# TDA2030.net
KiCad netlist of a schematic drawn in Altium Designer
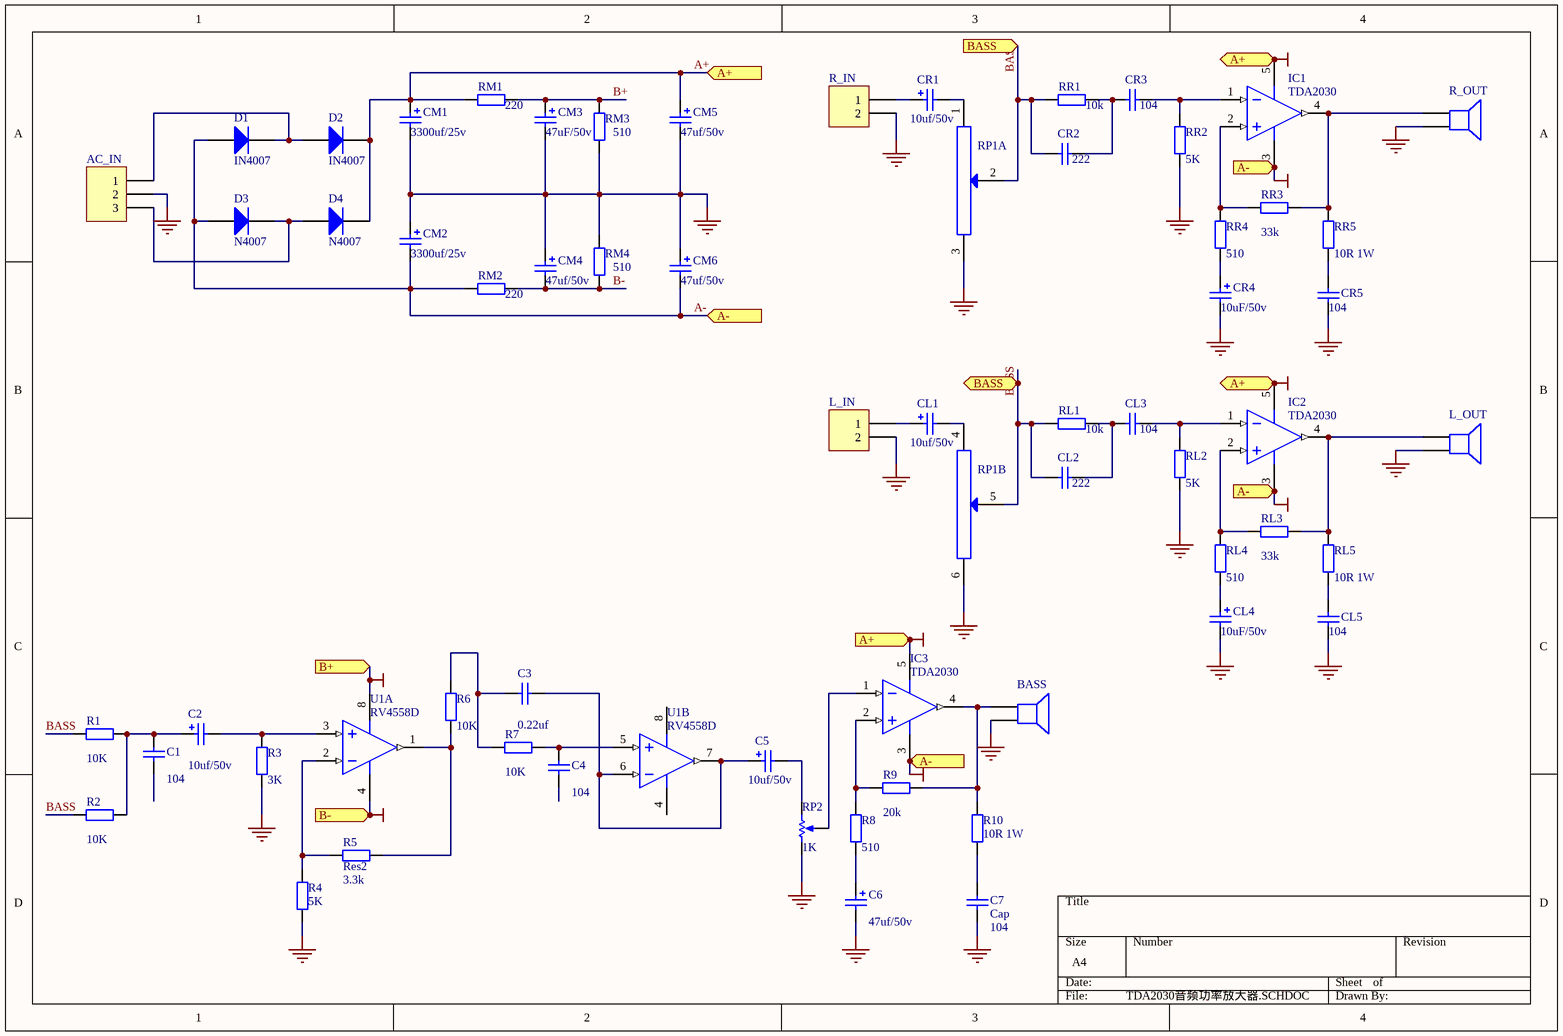
[diagram p0: TDA2030音频功率放大器.SCHDOC]

(export (version "E")
  (design (tool "Eeschema 10.0.6"))
  (components
    (comp (ref "AC_IN")
      (value "Header 3")
      (footprint "HDR1X3")
      (description "Header, 3-Pin")
      (fields (field (name "PUBLISHER") "Altium Limited"))
      (libsource (lib "Miscellaneous Connectors") (part "Header 3"))
    )
    (comp (ref "BASS")
      (value "Speaker")
      (footprint "PIN2")
      (description "Loudspeaker")
      (fields (field (name "PUBLISHER") "Altium Limited"))
      (libsource (lib "Miscellaneous Devices") (part "Speaker"))
    )
    (comp (ref "C1")
      (value "104")
      (footprint "RAD-0.3")
      (description "Capacitor")
      (fields (field (name "Comment") "Cap") (field (name "PUBLISHER") "Altium Limited"))
      (libsource (lib "Miscellaneous Devices") (part "Cap"))
    )
    (comp (ref "C2")
      (value "10uf/50v")
      (footprint "POLAR0.8")
      (description "Polarized Capacitor (Axial)")
      (fields (field (name "Comment") "Cap Pol2") (field (name "PUBLISHER") "Altium Limited"))
      (libsource (lib "Miscellaneous Devices") (part "Cap Pol2"))
    )
    (comp (ref "C3")
      (value "0.22uf")
      (footprint "RAD-0.3")
      (description "Capacitor")
      (fields (field (name "Comment") "Cap") (field (name "PUBLISHER") "Altium Limited"))
      (libsource (lib "Miscellaneous Devices") (part "Cap"))
    )
    (comp (ref "C4")
      (value "104")
      (footprint "RAD-0.3")
      (description "Capacitor")
      (fields (field (name "Comment") "Cap") (field (name "PUBLISHER") "Altium Limited"))
      (libsource (lib "Miscellaneous Devices") (part "Cap"))
    )
    (comp (ref "C5")
      (value "10uf/50v")
      (footprint "POLAR0.8")
      (description "Polarized Capacitor (Axial)")
      (fields (field (name "Comment") "Cap Pol2") (field (name "PUBLISHER") "Altium Limited"))
      (libsource (lib "Miscellaneous Devices") (part "Cap Pol2"))
    )
    (comp (ref "C6")
      (value "47uf/50v")
      (footprint "POLAR0.8")
      (description "Polarized Capacitor (Axial)")
      (fields (field (name "Comment") "Cap Pol2") (field (name "PUBLISHER") "Altium Limited"))
      (libsource (lib "Miscellaneous Devices") (part "Cap Pol2"))
    )
    (comp (ref "C7")
      (value "Cap")
      (footprint "RAD-0.3")
      (description "Capacitor")
      (fields (field (name "ALTIUM_VALUE") "104") (field (name "PUBLISHER") "Altium Limited"))
      (libsource (lib "Miscellaneous Devices") (part "Cap"))
    )
    (comp (ref "CL1")
      (value "10uf/50v")
      (footprint "POLAR0.8")
      (description "Polarized Capacitor (Axial)")
      (fields (field (name "Comment") "Cap Pol2") (field (name "PUBLISHER") "Altium Limited"))
      (libsource (lib "Miscellaneous Devices") (part "Cap Pol2"))
    )
    (comp (ref "CL2")
      (value "222")
      (footprint "RAD-0.3")
      (description "Capacitor")
      (fields (field (name "Comment") "Cap") (field (name "PUBLISHER") "Altium Limited"))
      (libsource (lib "Miscellaneous Devices") (part "Cap"))
    )
    (comp (ref "CL3")
      (value "104")
      (footprint "RAD-0.3")
      (description "Capacitor")
      (fields (field (name "Comment") "Cap") (field (name "PUBLISHER") "Altium Limited"))
      (libsource (lib "Miscellaneous Devices") (part "Cap"))
    )
    (comp (ref "CL4")
      (value "10uF/50v")
      (footprint "POLAR0.8")
      (description "Polarized Capacitor (Axial)")
      (fields (field (name "Comment") "Cap Pol2") (field (name "PUBLISHER") "Altium Limited"))
      (libsource (lib "Miscellaneous Devices") (part "Cap Pol2"))
    )
    (comp (ref "CL5")
      (value "104")
      (footprint "RAD-0.3")
      (description "Capacitor")
      (fields (field (name "Comment") "Cap") (field (name "PUBLISHER") "Altium Limited"))
      (libsource (lib "Miscellaneous Devices") (part "Cap"))
    )
    (comp (ref "CM1")
      (value "3300uf/25v")
      (footprint "POLAR0.8")
      (description "Polarized Capacitor (Axial)")
      (fields (field (name "Comment") "Cap Pol2") (field (name "PUBLISHER") "Altium Limited"))
      (libsource (lib "Miscellaneous Devices") (part "Cap Pol2"))
    )
    (comp (ref "CM2")
      (value "3300uf/25v")
      (footprint "POLAR0.8")
      (description "Polarized Capacitor (Axial)")
      (fields (field (name "Comment") "Cap Pol2") (field (name "PUBLISHER") "Altium Limited"))
      (libsource (lib "Miscellaneous Devices") (part "Cap Pol2"))
    )
    (comp (ref "CM3")
      (value "47uF/50v")
      (footprint "POLAR0.8")
      (description "Polarized Capacitor (Axial)")
      (fields (field (name "Comment") "Cap Pol2") (field (name "PUBLISHER") "Altium Limited"))
      (libsource (lib "Miscellaneous Devices") (part "Cap Pol2"))
    )
    (comp (ref "CM4")
      (value "47uf/50v")
      (footprint "POLAR0.8")
      (description "Polarized Capacitor (Axial)")
      (fields (field (name "Comment") "Cap Pol2") (field (name "PUBLISHER") "Altium Limited"))
      (libsource (lib "Miscellaneous Devices") (part "Cap Pol2"))
    )
    (comp (ref "CM5")
      (value "47uf/50v")
      (footprint "POLAR0.8")
      (description "Polarized Capacitor (Axial)")
      (fields (field (name "Comment") "Cap Pol2") (field (name "PUBLISHER") "Altium Limited"))
      (libsource (lib "Miscellaneous Devices") (part "Cap Pol2"))
    )
    (comp (ref "CM6")
      (value "47uf/50v")
      (footprint "POLAR0.8")
      (description "Polarized Capacitor (Axial)")
      (fields (field (name "Comment") "Cap Pol2") (field (name "PUBLISHER") "Altium Limited"))
      (libsource (lib "Miscellaneous Devices") (part "Cap Pol2"))
    )
    (comp (ref "CR1")
      (value "10uf/50v")
      (footprint "POLAR0.8")
      (description "Polarized Capacitor (Axial)")
      (fields (field (name "Comment") "Cap Pol2") (field (name "PUBLISHER") "Altium Limited"))
      (libsource (lib "Miscellaneous Devices") (part "Cap Pol2"))
    )
    (comp (ref "CR2")
      (value "222")
      (footprint "RAD-0.3")
      (description "Capacitor")
      (fields (field (name "Comment") "Cap") (field (name "PUBLISHER") "Altium Limited"))
      (libsource (lib "Miscellaneous Devices") (part "Cap"))
    )
    (comp (ref "CR3")
      (value "104")
      (footprint "RAD-0.3")
      (description "Capacitor")
      (fields (field (name "Comment") "Cap") (field (name "PUBLISHER") "Altium Limited"))
      (libsource (lib "Miscellaneous Devices") (part "Cap"))
    )
    (comp (ref "CR4")
      (value "10uF/50v")
      (footprint "POLAR0.8")
      (description "Polarized Capacitor (Axial)")
      (fields (field (name "Comment") "Cap Pol2") (field (name "PUBLISHER") "Altium Limited"))
      (libsource (lib "Miscellaneous Devices") (part "Cap Pol2"))
    )
    (comp (ref "CR5")
      (value "104")
      (footprint "RAD-0.3")
      (description "Capacitor")
      (fields (field (name "Comment") "Cap") (field (name "PUBLISHER") "Altium Limited"))
      (libsource (lib "Miscellaneous Devices") (part "Cap"))
    )
    (comp (ref "D1")
      (value "IN4007")
      (footprint "DIO10.46-5.3x2.8")
      (description "1 Amp General Purpose Rectifier")
      (fields (field (name "PUBLISHER") "Altium Limited"))
      (libsource (lib "Miscellaneous Devices") (part "Diode 1N4007"))
    )
    (comp (ref "D2")
      (value "IN4007")
      (footprint "DIO10.46-5.3x2.8")
      (description "1 Amp General Purpose Rectifier")
      (fields (field (name "PUBLISHER") "Altium Limited"))
      (libsource (lib "Miscellaneous Devices") (part "Diode 1N4007"))
    )
    (comp (ref "D3")
      (value "N4007")
      (footprint "DIO10.46-5.3x2.8")
      (description "1 Amp General Purpose Rectifier")
      (fields (field (name "PUBLISHER") "Altium Limited"))
      (libsource (lib "Miscellaneous Devices") (part "Diode 1N4007"))
    )
    (comp (ref "D4")
      (value "N4007")
      (footprint "DIO10.46-5.3x2.8")
      (description "1 Amp General Purpose Rectifier")
      (fields (field (name "PUBLISHER") "Altium Limited"))
      (libsource (lib "Miscellaneous Devices") (part "Diode 1N4007"))
    )
    (comp (ref "IC1") (value "TDA2030") (libsource (lib "TDA2030音频功率放大器") (part "TDA2030")))
    (comp (ref "IC2") (value "TDA2030") (libsource (lib "TDA2030音频功率放大器") (part "TDA2030")))
    (comp (ref "IC3") (value "TDA2030") (libsource (lib "TDA2030音频功率放大器") (part "TDA2030")))
    (comp (ref "L_IN")
      (value "Header 2")
      (footprint "HDR1X2")
      (description "Header, 2-Pin")
      (fields (field (name "PUBLISHER") "Altium Limited"))
      (libsource (lib "Miscellaneous Connectors") (part "Header 2"))
    )
    (comp (ref "L_OUT")
      (value "Speaker")
      (footprint "PIN2")
      (description "Loudspeaker")
      (fields (field (name "PUBLISHER") "Altium Limited"))
      (libsource (lib "Miscellaneous Devices") (part "Speaker"))
    )
    (comp (ref "R1")
      (value "10K")
      (footprint "AXIAL-0.4")
      (description "Resistor")
      (fields (field (name "Comment") "Res2") (field (name "PUBLISHER") "Altium Limited"))
      (libsource (lib "Miscellaneous Devices") (part "Res2"))
    )
    (comp (ref "R2")
      (value "10K")
      (footprint "AXIAL-0.4")
      (description "Resistor")
      (fields (field (name "Comment") "Res2") (field (name "PUBLISHER") "Altium Limited"))
      (libsource (lib "Miscellaneous Devices") (part "Res2"))
    )
    (comp (ref "R3")
      (value "3K")
      (footprint "AXIAL-0.4")
      (description "Resistor")
      (fields (field (name "Comment") "Res2") (field (name "PUBLISHER") "Altium Limited"))
      (libsource (lib "") (part "Res2_1"))
    )
    (comp (ref "R4")
      (value "5K")
      (footprint "AXIAL-0.4")
      (description "Resistor")
      (fields (field (name "Comment") "Res2") (field (name "PUBLISHER") "Altium Limited"))
      (libsource (lib "") (part "Res2_1"))
    )
    (comp (ref "R5")
      (value "Res2")
      (footprint "AXIAL-0.4")
      (description "Resistor")
      (fields (field (name "ALTIUM_VALUE") "3.3k") (field (name "PUBLISHER") "Altium Limited"))
      (libsource (lib "") (part "Res2_3"))
    )
    (comp (ref "R6")
      (value "10K")
      (footprint "AXIAL-0.4")
      (description "Resistor")
      (fields (field (name "Comment") "Res2") (field (name "PUBLISHER") "Altium Limited"))
      (libsource (lib "") (part "Res2_2"))
    )
    (comp (ref "R7")
      (value "10K")
      (footprint "AXIAL-0.4")
      (description "Resistor")
      (fields (field (name "Comment") "Res2") (field (name "PUBLISHER") "Altium Limited"))
      (libsource (lib "Miscellaneous Devices") (part "Res2"))
    )
    (comp (ref "R8")
      (value "510")
      (footprint "AXIAL-0.4")
      (description "Resistor")
      (fields (field (name "Comment") "Res2") (field (name "PUBLISHER") "Altium Limited"))
      (libsource (lib "") (part "Res2_1"))
    )
    (comp (ref "R9")
      (value "20k")
      (footprint "AXIAL-0.4")
      (description "Resistor")
      (fields (field (name "Comment") "Res2") (field (name "PUBLISHER") "Altium Limited"))
      (libsource (lib "Miscellaneous Devices") (part "Res2"))
    )
    (comp (ref "R10")
      (value "10R 1W")
      (footprint "AXIAL-0.4")
      (description "Resistor")
      (fields (field (name "Comment") "Res2") (field (name "PUBLISHER") "Altium Limited"))
      (libsource (lib "") (part "Res2_1"))
    )
    (comp (ref "RL1")
      (value "10k")
      (footprint "AXIAL-0.4")
      (description "Resistor")
      (fields (field (name "Comment") "Res2") (field (name "PUBLISHER") "Altium Limited"))
      (libsource (lib "Miscellaneous Devices") (part "Res2"))
    )
    (comp (ref "RL2")
      (value "5K")
      (footprint "AXIAL-0.4")
      (description "Resistor")
      (fields (field (name "Comment") "Res2") (field (name "PUBLISHER") "Altium Limited"))
      (libsource (lib "") (part "Res2_1"))
    )
    (comp (ref "RL3")
      (value "33k")
      (footprint "AXIAL-0.4")
      (description "Resistor")
      (fields (field (name "Comment") "Res2") (field (name "PUBLISHER") "Altium Limited"))
      (libsource (lib "") (part "Res2_3"))
    )
    (comp (ref "RL4")
      (value "510")
      (footprint "AXIAL-0.4")
      (description "Resistor")
      (fields (field (name "Comment") "Res2") (field (name "PUBLISHER") "Altium Limited"))
      (libsource (lib "") (part "Res2_1"))
    )
    (comp (ref "RL5")
      (value "10R 1W")
      (footprint "AXIAL-0.4")
      (description "Resistor")
      (fields (field (name "Comment") "Res2") (field (name "PUBLISHER") "Altium Limited"))
      (libsource (lib "") (part "Res2_2"))
    )
    (comp (ref "RM1")
      (value "220")
      (footprint "AXIAL-0.4")
      (description "Resistor")
      (fields (field (name "Comment") "Res2") (field (name "PUBLISHER") "Altium Limited"))
      (libsource (lib "Miscellaneous Devices") (part "Res2"))
    )
    (comp (ref "RM2")
      (value "220")
      (footprint "AXIAL-0.4")
      (description "Resistor")
      (fields (field (name "Comment") "Res2") (field (name "PUBLISHER") "Altium Limited"))
      (libsource (lib "Miscellaneous Devices") (part "Res2"))
    )
    (comp (ref "RM3")
      (value "510")
      (footprint "AXIAL-0.4")
      (description "Resistor")
      (fields (field (name "Comment") "Res2") (field (name "PUBLISHER") "Altium Limited"))
      (libsource (lib "") (part "Res2_1"))
    )
    (comp (ref "RM4")
      (value "510")
      (footprint "AXIAL-0.4")
      (description "Resistor")
      (fields (field (name "Comment") "Res2") (field (name "PUBLISHER") "Altium Limited"))
      (libsource (lib "") (part "Res2_1"))
    )
    (comp (ref "RP1") (value "POT3") (footprint "BK09") (libsource (lib "47耳放设计") (part "POT3")))
    (comp (ref "RP2")
      (value "1K")
      (footprint "VR5")
      (description "Potentiometer")
      (fields (field (name "Comment") "POT2") (field (name "PUBLISHER") "Altium Limited"))
      (libsource (lib "Miscellaneous Devices") (part "RPot"))
    )
    (comp (ref "RR1")
      (value "10k")
      (footprint "AXIAL-0.4")
      (description "Resistor")
      (fields (field (name "Comment") "Res2") (field (name "PUBLISHER") "Altium Limited"))
      (libsource (lib "Miscellaneous Devices") (part "Res2"))
    )
    (comp (ref "RR2")
      (value "5K")
      (footprint "AXIAL-0.4")
      (description "Resistor")
      (fields (field (name "Comment") "Res2") (field (name "PUBLISHER") "Altium Limited"))
      (libsource (lib "") (part "Res2_1"))
    )
    (comp (ref "RR3")
      (value "33k")
      (footprint "AXIAL-0.4")
      (description "Resistor")
      (fields (field (name "Comment") "Res2") (field (name "PUBLISHER") "Altium Limited"))
      (libsource (lib "") (part "Res2_3"))
    )
    (comp (ref "RR4")
      (value "510")
      (footprint "AXIAL-0.4")
      (description "Resistor")
      (fields (field (name "Comment") "Res2") (field (name "PUBLISHER") "Altium Limited"))
      (libsource (lib "") (part "Res2_1"))
    )
    (comp (ref "RR5")
      (value "10R 1W")
      (footprint "AXIAL-0.4")
      (description "Resistor")
      (fields (field (name "Comment") "Res2") (field (name "PUBLISHER") "Altium Limited"))
      (libsource (lib "") (part "Res2_2"))
    )
    (comp (ref "R_IN")
      (value "Header 2")
      (footprint "HDR1X2")
      (description "Header, 2-Pin")
      (fields (field (name "PUBLISHER") "Altium Limited"))
      (libsource (lib "Miscellaneous Connectors") (part "Header 2"))
    )
    (comp (ref "R_OUT")
      (value "Speaker")
      (footprint "PIN2")
      (description "Loudspeaker")
      (fields (field (name "PUBLISHER") "Altium Limited"))
      (libsource (lib "Miscellaneous Devices") (part "Speaker"))
    )
    (comp (ref "U1")
      (value "RV4558D")
      (footprint "D008")
      (description "Dual High-Performance Operational Amplifier")
      (fields (field (name "PUBLISHER") "Altium Limited"))
      (libsource (lib "TDA2030音频功率放大器") (part "RV4558D"))
    )
  )
  (nets
    (net (code "1") (name "/BASS") (class "Default")
      (node (ref "CL2") (pin "1") (pinfunction "1_1") (pintype "passive"))
      (node (ref "CR2") (pin "1") (pinfunction "1_1") (pintype "passive"))
      (node (ref "R1") (pin "1") (pinfunction "1_1") (pintype "passive"))
      (node (ref "R2") (pin "1") (pinfunction "1_1") (pintype "passive"))
      (node (ref "RL1") (pin "1") (pinfunction "1_1") (pintype "passive"))
      (node (ref "RP1") (pin "2") (pinfunction "2_2") (pintype "passive"))
      (node (ref "RP1") (pin "5") (pinfunction "5_5") (pintype "passive"))
      (node (ref "RR1") (pin "1") (pinfunction "1_1") (pintype "passive"))
    )
    (net (code "2") (name "A+") (class "Default")
      (node (ref "CM1") (pin "1") (pinfunction "1_1") (pintype "passive"))
      (node (ref "CM5") (pin "1") (pinfunction "1_1") (pintype "passive"))
      (node (ref "D2") (pin "2") (pinfunction "K_2") (pintype "passive"))
      (node (ref "D4") (pin "2") (pinfunction "K_2") (pintype "passive"))
      (node (ref "IC1") (pin "5") (pinfunction "V+_5") (pintype "power_in"))
      (node (ref "IC2") (pin "5") (pinfunction "V+_5") (pintype "power_in"))
      (node (ref "IC3") (pin "5") (pinfunction "V+_5") (pintype "power_in"))
      (node (ref "RM1") (pin "1") (pinfunction "1_1") (pintype "passive"))
    )
    (net (code "3") (name "A-") (class "Default")
      (node (ref "CM2") (pin "2") (pinfunction "2_2") (pintype "passive"))
      (node (ref "CM6") (pin "2") (pinfunction "2_2") (pintype "passive"))
      (node (ref "D1") (pin "1") (pinfunction "A_1") (pintype "passive"))
      (node (ref "D3") (pin "1") (pinfunction "A_1") (pintype "passive"))
      (node (ref "IC1") (pin "3") (pinfunction "V-_3") (pintype "power_in"))
      (node (ref "IC2") (pin "3") (pinfunction "V-_3") (pintype "power_in"))
      (node (ref "IC3") (pin "3") (pinfunction "V-_3") (pintype "power_in"))
      (node (ref "RM2") (pin "1") (pinfunction "1_1") (pintype "passive"))
    )
    (net (code "4") (name "B+") (class "Default")
      (node (ref "CM3") (pin "1") (pinfunction "1_1") (pintype "passive"))
      (node (ref "RM1") (pin "2") (pinfunction "2_2") (pintype "passive"))
      (node (ref "RM3") (pin "2") (pinfunction "2_2") (pintype "passive"))
      (node (ref "U1") (pin "8") (pinfunction "V+_8") (pintype "power_in"))
    )
    (net (code "5") (name "B-") (class "Default")
      (node (ref "CM4") (pin "2") (pinfunction "2_2") (pintype "passive"))
      (node (ref "RM2") (pin "2") (pinfunction "2_2") (pintype "passive"))
      (node (ref "RM4") (pin "1") (pinfunction "1_1") (pintype "passive"))
      (node (ref "U1") (pin "4") (pinfunction "V-_4") (pintype "power_in"))
    )
    (net (code "6") (name "GND") (class "Default")
      (node (ref "AC_IN") (pin "2") (pinfunction "2_2") (pintype "passive"))
      (node (ref "BASS") (pin "2") (pinfunction "2_2") (pintype "passive"))
      (node (ref "C6") (pin "2") (pinfunction "2_2") (pintype "passive"))
      (node (ref "C7") (pin "2") (pinfunction "2_2") (pintype "passive"))
      (node (ref "CL4") (pin "2") (pinfunction "2_2") (pintype "passive"))
      (node (ref "CL5") (pin "1") (pinfunction "1_1") (pintype "passive"))
      (node (ref "CM1") (pin "2") (pinfunction "2_2") (pintype "passive"))
      (node (ref "CM2") (pin "1") (pinfunction "1_1") (pintype "passive"))
      (node (ref "CM3") (pin "2") (pinfunction "2_2") (pintype "passive"))
      (node (ref "CM4") (pin "1") (pinfunction "1_1") (pintype "passive"))
      (node (ref "CM5") (pin "2") (pinfunction "2_2") (pintype "passive"))
      (node (ref "CM6") (pin "1") (pinfunction "1_1") (pintype "passive"))
      (node (ref "CR4") (pin "2") (pinfunction "2_2") (pintype "passive"))
      (node (ref "CR5") (pin "1") (pinfunction "1_1") (pintype "passive"))
      (node (ref "L_IN") (pin "2") (pinfunction "2_2") (pintype "passive"))
      (node (ref "L_OUT") (pin "2") (pinfunction "2_2") (pintype "passive"))
      (node (ref "R3") (pin "1") (pinfunction "1_1") (pintype "passive"))
      (node (ref "R4") (pin "1") (pinfunction "1_1") (pintype "passive"))
      (node (ref "RL2") (pin "1") (pinfunction "1_1") (pintype "passive"))
      (node (ref "RM3") (pin "1") (pinfunction "1_1") (pintype "passive"))
      (node (ref "RM4") (pin "2") (pinfunction "2_2") (pintype "passive"))
      (node (ref "RP1") (pin "3") (pinfunction "3_3") (pintype "passive"))
      (node (ref "RP1") (pin "6") (pinfunction "6_6") (pintype "passive"))
      (node (ref "RP2") (pin "1") (pinfunction "TOP_1") (pintype "passive"))
      (node (ref "RR2") (pin "1") (pinfunction "1_1") (pintype "passive"))
      (node (ref "R_IN") (pin "2") (pinfunction "2_2") (pintype "passive"))
      (node (ref "R_OUT") (pin "2") (pinfunction "2_2") (pintype "passive"))
    )
    (net (code "7") (name "Net-(C1-Pad2)") (class "Default")
      (node (ref "C1") (pin "2") (pinfunction "2_2") (pintype "passive"))
      (node (ref "C2") (pin "1") (pinfunction "1_1") (pintype "passive"))
      (node (ref "R1") (pin "2") (pinfunction "2_2") (pintype "passive"))
      (node (ref "R2") (pin "2") (pinfunction "2_2") (pintype "passive"))
    )
    (net (code "8") (name "Net-(C3-Pad2)") (class "Default")
      (node (ref "C3") (pin "2") (pinfunction "2_2") (pintype "passive"))
      (node (ref "R6") (pin "1") (pinfunction "1_1") (pintype "passive"))
      (node (ref "R7") (pin "1") (pinfunction "1_1") (pintype "passive"))
    )
    (net (code "9") (name "Net-(C6-Pad1)") (class "Default")
      (node (ref "C6") (pin "1") (pinfunction "1_1") (pintype "passive"))
      (node (ref "R8") (pin "1") (pinfunction "1_1") (pintype "passive"))
    )
    (net (code "10") (name "Net-(C7-Pad1)") (class "Default")
      (node (ref "C7") (pin "1") (pinfunction "1_1") (pintype "passive"))
      (node (ref "R10") (pin "1") (pinfunction "1_1") (pintype "passive"))
    )
    (net (code "11") (name "Net-(CL1-Pad1)") (class "Default")
      (node (ref "CL1") (pin "1") (pinfunction "1_1") (pintype "passive"))
      (node (ref "L_IN") (pin "1") (pinfunction "1_1") (pintype "passive"))
    )
    (net (code "12") (name "Net-(CL1-Pad2)") (class "Default")
      (node (ref "CL1") (pin "2") (pinfunction "2_2") (pintype "passive"))
      (node (ref "RP1") (pin "4") (pinfunction "4_4") (pintype "passive"))
    )
    (net (code "13") (name "Net-(CL2-Pad2)") (class "Default")
      (node (ref "CL2") (pin "2") (pinfunction "2_2") (pintype "passive"))
      (node (ref "CL3") (pin "1") (pinfunction "1_1") (pintype "passive"))
      (node (ref "RL1") (pin "2") (pinfunction "2_2") (pintype "passive"))
    )
    (net (code "14") (name "Net-(CL4-Pad1)") (class "Default")
      (node (ref "CL4") (pin "1") (pinfunction "1_1") (pintype "passive"))
      (node (ref "RL4") (pin "1") (pinfunction "1_1") (pintype "passive"))
    )
    (net (code "15") (name "Net-(CL5-Pad2)") (class "Default")
      (node (ref "CL5") (pin "2") (pinfunction "2_2") (pintype "passive"))
      (node (ref "RL5") (pin "2") (pinfunction "2_2") (pintype "passive"))
    )
    (net (code "16") (name "Net-(CR1-Pad1)") (class "Default")
      (node (ref "CR1") (pin "1") (pinfunction "1_1") (pintype "passive"))
      (node (ref "R_IN") (pin "1") (pinfunction "1_1") (pintype "passive"))
    )
    (net (code "17") (name "Net-(CR2-Pad2)") (class "Default")
      (node (ref "CR2") (pin "2") (pinfunction "2_2") (pintype "passive"))
      (node (ref "CR3") (pin "1") (pinfunction "1_1") (pintype "passive"))
      (node (ref "RR1") (pin "2") (pinfunction "2_2") (pintype "passive"))
    )
    (net (code "18") (name "Net-(CR4-Pad1)") (class "Default")
      (node (ref "CR4") (pin "1") (pinfunction "1_1") (pintype "passive"))
      (node (ref "RR4") (pin "1") (pinfunction "1_1") (pintype "passive"))
    )
    (net (code "19") (name "Net-(CR5-Pad2)") (class "Default")
      (node (ref "CR5") (pin "2") (pinfunction "2_2") (pintype "passive"))
      (node (ref "RR5") (pin "2") (pinfunction "2_2") (pintype "passive"))
    )
    (net (code "20") (name "Net-(D1-K)") (class "Default")
      (node (ref "AC_IN") (pin "1") (pinfunction "1_1") (pintype "passive"))
      (node (ref "D1") (pin "2") (pinfunction "K_2") (pintype "passive"))
      (node (ref "D2") (pin "1") (pinfunction "A_1") (pintype "passive"))
    )
    (net (code "21") (name "Net-(D3-K)") (class "Default")
      (node (ref "AC_IN") (pin "3") (pinfunction "3_3") (pintype "passive"))
      (node (ref "D3") (pin "2") (pinfunction "K_2") (pintype "passive"))
      (node (ref "D4") (pin "1") (pinfunction "A_1") (pintype "passive"))
    )
    (net (code "22") (name "Net-(IC1-IN+)") (class "Default")
      (node (ref "IC1") (pin "2") (pinfunction "IN+_2") (pintype "input"))
      (node (ref "RR3") (pin "2") (pinfunction "2_2") (pintype "passive"))
      (node (ref "RR4") (pin "2") (pinfunction "2_2") (pintype "passive"))
    )
    (net (code "23") (name "Net-(IC1-IN-)") (class "Default")
      (node (ref "CR3") (pin "2") (pinfunction "2_2") (pintype "passive"))
      (node (ref "IC1") (pin "1") (pinfunction "IN-_1") (pintype "input"))
      (node (ref "RR2") (pin "2") (pinfunction "2_2") (pintype "passive"))
    )
    (net (code "24") (name "Net-(IC1-OUT)") (class "Default")
      (node (ref "IC1") (pin "4") (pinfunction "OUT_4") (pintype "output"))
      (node (ref "RR3") (pin "1") (pinfunction "1_1") (pintype "passive"))
      (node (ref "RR5") (pin "1") (pinfunction "1_1") (pintype "passive"))
      (node (ref "R_OUT") (pin "1") (pinfunction "1_1") (pintype "passive"))
    )
    (net (code "25") (name "Net-(IC2-IN+)") (class "Default")
      (node (ref "IC2") (pin "2") (pinfunction "IN+_2") (pintype "input"))
      (node (ref "RL3") (pin "2") (pinfunction "2_2") (pintype "passive"))
      (node (ref "RL4") (pin "2") (pinfunction "2_2") (pintype "passive"))
    )
    (net (code "26") (name "Net-(IC2-IN-)") (class "Default")
      (node (ref "CL3") (pin "2") (pinfunction "2_2") (pintype "passive"))
      (node (ref "IC2") (pin "1") (pinfunction "IN-_1") (pintype "input"))
      (node (ref "RL2") (pin "2") (pinfunction "2_2") (pintype "passive"))
    )
    (net (code "27") (name "Net-(IC2-OUT)") (class "Default")
      (node (ref "IC2") (pin "4") (pinfunction "OUT_4") (pintype "output"))
      (node (ref "L_OUT") (pin "1") (pinfunction "1_1") (pintype "passive"))
      (node (ref "RL3") (pin "1") (pinfunction "1_1") (pintype "passive"))
      (node (ref "RL5") (pin "1") (pinfunction "1_1") (pintype "passive"))
    )
    (net (code "28") (name "Net-(IC3-IN+)") (class "Default")
      (node (ref "IC3") (pin "2") (pinfunction "IN+_2") (pintype "input"))
      (node (ref "R8") (pin "2") (pinfunction "2_2") (pintype "passive"))
      (node (ref "R9") (pin "1") (pinfunction "1_1") (pintype "passive"))
    )
    (net (code "29") (name "Net-(IC3-IN-)") (class "Default")
      (node (ref "IC3") (pin "1") (pinfunction "IN-_1") (pintype "input"))
      (node (ref "RP2") (pin "3") (pinfunction "TAP_3") (pintype "passive"))
    )
    (net (code "30") (name "Net-(IC3-OUT)") (class "Default")
      (node (ref "BASS") (pin "1") (pinfunction "1_1") (pintype "passive"))
      (node (ref "IC3") (pin "4") (pinfunction "OUT_4") (pintype "output"))
      (node (ref "R10") (pin "2") (pinfunction "2_2") (pintype "passive"))
      (node (ref "R9") (pin "2") (pinfunction "2_2") (pintype "passive"))
    )
    (net (code "31") (name "Net-(RP1A-0)") (class "Default")
      (node (ref "CR1") (pin "2") (pinfunction "2_2") (pintype "passive"))
      (node (ref "RP1") (pin "1") (pinfunction "0_1") (pintype "passive"))
    )
    (net (code "32") (name "Net-(RP2-BOT)") (class "Default")
      (node (ref "C5") (pin "2") (pinfunction "2_2") (pintype "passive"))
      (node (ref "RP2") (pin "2") (pinfunction "BOT_2") (pintype "passive"))
    )
    (net (code "33") (name "Net-(U1A-IN+)") (class "Default")
      (node (ref "C2") (pin "2") (pinfunction "2_2") (pintype "passive"))
      (node (ref "R3") (pin "2") (pinfunction "2_2") (pintype "passive"))
      (node (ref "U1") (pin "3") (pinfunction "IN+_3") (pintype "input"))
    )
    (net (code "34") (name "Net-(U1A-IN-)") (class "Default")
      (node (ref "R4") (pin "2") (pinfunction "2_2") (pintype "passive"))
      (node (ref "R5") (pin "2") (pinfunction "2_2") (pintype "passive"))
      (node (ref "U1") (pin "2") (pinfunction "IN-_2") (pintype "input"))
    )
    (net (code "35") (name "Net-(U1A-OUT)") (class "Default")
      (node (ref "R5") (pin "1") (pinfunction "1_1") (pintype "passive"))
      (node (ref "R6") (pin "2") (pinfunction "2_2") (pintype "passive"))
      (node (ref "U1") (pin "1") (pinfunction "OUT_1") (pintype "output"))
    )
    (net (code "36") (name "Net-(U1B-IN+)") (class "Default")
      (node (ref "C4") (pin "1") (pinfunction "1_1") (pintype "passive"))
      (node (ref "R7") (pin "2") (pinfunction "2_2") (pintype "passive"))
      (node (ref "U1") (pin "5") (pinfunction "IN+_5") (pintype "input"))
    )
    (net (code "37") (name "Net-(U1B-IN-)") (class "Default")
      (node (ref "C3") (pin "1") (pinfunction "1_1") (pintype "passive"))
      (node (ref "C5") (pin "1") (pinfunction "1_1") (pintype "passive"))
      (node (ref "U1") (pin "6") (pinfunction "IN-_6") (pintype "input"))
      (node (ref "U1") (pin "7") (pinfunction "OUT_7") (pintype "output"))
    )
    (net (code "38") (name "unconnected-(C1-Pad1)") (class "Default")
      (node (ref "C1") (pin "1") (pinfunction "1_1") (pintype "passive"))
    )
    (net (code "39") (name "unconnected-(C4-Pad2)") (class "Default")
      (node (ref "C4") (pin "2") (pinfunction "2_2") (pintype "passive"))
    )
    (net (code "40") (name "unconnected-(U1B-V+-Pad8)") (class "Default")
      (node (ref "U1") (pin "8") (pinfunction "V+_8") (pintype "power_in"))
    )
    (net (code "41") (name "unconnected-(U1B-V--Pad4)") (class "Default")
      (node (ref "U1") (pin "4") (pinfunction "V-_4") (pintype "power_in"))
    )
  )
)
